# LM2596.net
KiCad netlist of a schematic drawn in Altium Designer
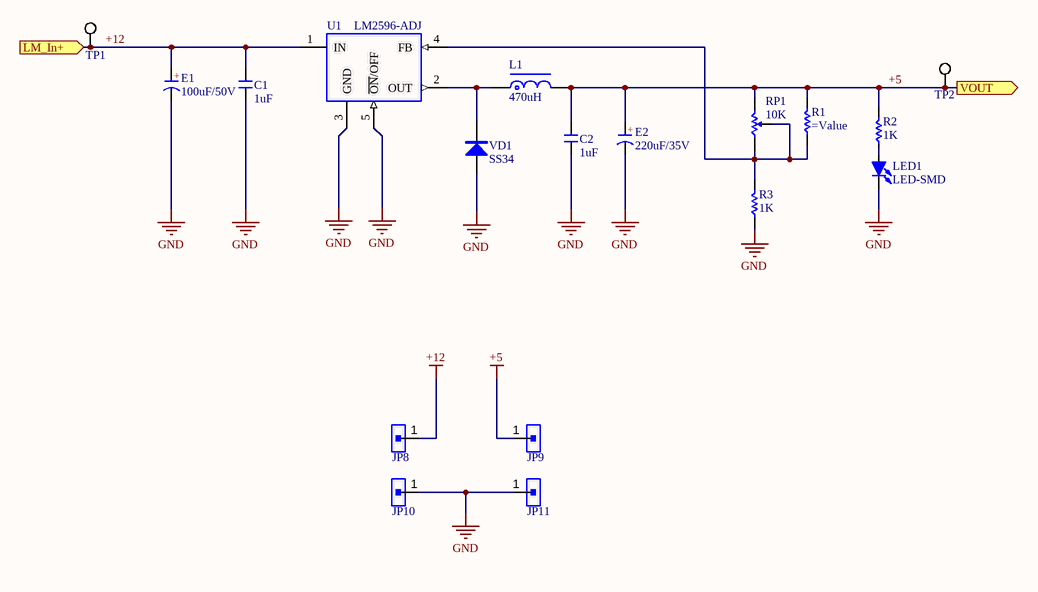
[diagram p0: LM2596.SchDoc]

(export (version "E")
  (design (tool "Eeschema 10.0.6"))
  (components
    (comp (ref "C1")
      (value "1uF")
      (footprint "C 0805")
      (description "Non-polar patch capacitor")
      (fields (field (name "版权归属") "源创客"))
      (libsource (lib "Passive (Resistor-Capacitor-Inductor-Veristor-Ferrite)") (part "C"))
    )
    (comp (ref "C2")
      (value "1uF")
      (footprint "C 0805")
      (description "Non-polar patch capacitor")
      (fields (field (name "版权归属") "源创客"))
      (libsource (lib "Passive (Resistor-Capacitor-Inductor-Veristor-Ferrite)") (part "C"))
    )
    (comp (ref "E1")
      (value "100uF/50V")
      (footprint "CM E(8*10.2)")
      (description "Chip electrolytic capacitor")
      (fields (field (name "版权归属") "源创客"))
      (libsource (lib "Passive (Resistor-Capacitor-Inductor-Veristor-Ferrite)") (part "C-CM"))
    )
    (comp (ref "E2")
      (value "220uF/35V")
      (footprint "CM E(8*10.2)")
      (description "Chip electrolytic capacitor")
      (fields (field (name "版权归属") "源创客"))
      (libsource (lib "Passive (Resistor-Capacitor-Inductor-Veristor-Ferrite)") (part "C-CM"))
    )
    (comp (ref "JP8")
      (value "HDR-1X1")
      (footprint "HDR-1X1")
      (description "1P Connector")
      (fields (field (name "版权归属") "源创客"))
      (libsource (lib "") (part "Header 1_1"))
    )
    (comp (ref "JP9")
      (value "HDR-1X1")
      (footprint "HDR-1X1")
      (description "1P Connector")
      (fields (field (name "版权归属") "源创客"))
      (libsource (lib "Connectors") (part "Header 1"))
    )
    (comp (ref "JP10")
      (value "HDR-1X1")
      (footprint "HDR-1X1")
      (description "1P Connector")
      (fields (field (name "版权归属") "源创客"))
      (libsource (lib "") (part "Header 1_1"))
    )
    (comp (ref "JP11")
      (value "HDR-1X1")
      (footprint "HDR-1X1")
      (description "1P Connector")
      (fields (field (name "版权归属") "源创客"))
      (libsource (lib "Connectors") (part "Header 1"))
    )
    (comp (ref "L1")
      (value "470uH")
      (footprint "CDRH127")
      (description "Power shielded inductor")
      (fields (field (name "版权归属") "源创客"))
      (libsource (lib "Passive (Resistor-Capacitor-Inductor-Veristor-Ferrite)") (part "L-CDRH"))
    )
    (comp (ref "LED1")
      (value "LED-SMD")
      (footprint "LED 0805R")
      (description "Patch LED")
      (fields (field (name "版权归属") "源创客"))
      (libsource (lib "LED") (part "LED-SMD"))
    )
    (comp (ref "R1")
      (value "~")
      (footprint "R 0805")
      (description "Chip resistor")
      (fields (field (name "版权归属") "源创客"))
      (libsource (lib "Passive (Resistor-Capacitor-Inductor-Veristor-Ferrite)") (part "R"))
    )
    (comp (ref "R2")
      (value "1K")
      (footprint "R 0805")
      (description "Chip resistor")
      (fields (field (name "版权归属") "源创客"))
      (libsource (lib "Passive (Resistor-Capacitor-Inductor-Veristor-Ferrite)") (part "R"))
    )
    (comp (ref "R3")
      (value "1K")
      (footprint "R 0805")
      (description "Chip resistor")
      (fields (field (name "版权归属") "源创客"))
      (libsource (lib "Passive (Resistor-Capacitor-Inductor-Veristor-Ferrite)") (part "R"))
    )
    (comp (ref "RP1")
      (value "10K")
      (footprint "3296W")
      (description "Plug-in potentiometer")
      (fields (field (name "版权归属") "源创客"))
      (libsource (lib "Passive (Resistor-Capacitor-Inductor-Veristor-Ferrite)") (part "RP-THD"))
    )
    (comp (ref "TP1")
      (value "Test Point Pad")
      (footprint "TP15")
      (fields (field (name "DESIGNER") "Eng. Saeid Jorablo"))
      (libsource (lib "Test Point") (part "Test Point Pad"))
    )
    (comp (ref "TP2")
      (value "Test Point Pad")
      (footprint "TP15")
      (fields (field (name "DESIGNER") "Eng. Saeid Jorablo"))
      (libsource (lib "Test Point") (part "Test Point Pad"))
    )
    (comp (ref "U1")
      (value "LM2596-ADJ")
      (footprint "TO263-5A")
      (description "DC step-down chip")
      (fields (field (name "版权归属") "源创客"))
      (libsource (lib "Integrated Circuit") (part "LM2596"))
    )
    (comp (ref "VD1")
      (value "SS34")
      (footprint "SMA")
      (description "Schottky diodes")
      (fields (field (name "版权归属") "源创客"))
      (libsource (lib "Diode-Zener-Rectifier Bridge") (part "SS34"))
    )
  )
  (nets
    (net (code "1") (name "+5") (class "Default")
      (node (ref "C2") (pin "2") (pinfunction "2_2") (pintype "passive"))
      (node (ref "E2") (pin "1") (pinfunction "A_1") (pintype "passive"))
      (node (ref "JP9") (pin "1") (pintype "passive"))
      (node (ref "L1") (pin "2") (pinfunction "2_2") (pintype "passive"))
      (node (ref "R1") (pin "2") (pinfunction "2_2") (pintype "passive"))
      (node (ref "R2") (pin "2") (pinfunction "2_2") (pintype "passive"))
      (node (ref "RP1") (pin "2") (pinfunction "2_2") (pintype "passive"))
      (node (ref "TP2") (pin "1") (pinfunction "1_1") (pintype "passive"))
    )
    (net (code "2") (name "+12") (class "Default")
      (node (ref "C1") (pin "2") (pinfunction "2_2") (pintype "passive"))
      (node (ref "E1") (pin "1") (pinfunction "A_1") (pintype "passive"))
      (node (ref "JP8") (pin "1") (pintype "passive"))
      (node (ref "TP1") (pin "1") (pinfunction "1_1") (pintype "passive"))
      (node (ref "U1") (pin "1") (pinfunction "IN_1") (pintype "power_in"))
    )
    (net (code "3") (name "GND") (class "Default")
      (node (ref "C1") (pin "1") (pinfunction "1_1") (pintype "passive"))
      (node (ref "C2") (pin "1") (pinfunction "1_1") (pintype "passive"))
      (node (ref "E1") (pin "2") (pinfunction "K_2") (pintype "passive"))
      (node (ref "E2") (pin "2") (pinfunction "K_2") (pintype "passive"))
      (node (ref "JP10") (pin "1") (pintype "passive"))
      (node (ref "JP11") (pin "1") (pintype "passive"))
      (node (ref "LED1") (pin "2") (pinfunction "K_2") (pintype "passive"))
      (node (ref "R3") (pin "1") (pinfunction "1_1") (pintype "passive"))
      (node (ref "U1") (pin "3") (pinfunction "GND_3") (pintype "power_in"))
      (node (ref "U1") (pin "5") (pinfunction "~{ON}/OFF_5") (pintype "input"))
      (node (ref "VD1") (pin "1") (pinfunction "A_1") (pintype "passive"))
    )
    (net (code "4") (name "Net-(LED1-A)") (class "Default")
      (node (ref "LED1") (pin "1") (pinfunction "A_1") (pintype "passive"))
      (node (ref "R2") (pin "1") (pinfunction "1_1") (pintype "passive"))
    )
    (net (code "5") (name "Net-(U1-FB)") (class "Default")
      (node (ref "R1") (pin "1") (pinfunction "1_1") (pintype "passive"))
      (node (ref "R3") (pin "2") (pinfunction "2_2") (pintype "passive"))
      (node (ref "RP1") (pin "1") (pinfunction "1_1") (pintype "passive"))
      (node (ref "RP1") (pin "ADJ") (pinfunction "ADJ_ADJ") (pintype "passive"))
      (node (ref "U1") (pin "4") (pinfunction "FB_4") (pintype "input"))
    )
    (net (code "6") (name "Net-(U1-OUT)") (class "Default")
      (node (ref "L1") (pin "1") (pinfunction "1_1") (pintype "passive"))
      (node (ref "U1") (pin "2") (pinfunction "OUT_2") (pintype "output"))
      (node (ref "VD1") (pin "2") (pinfunction "K_2") (pintype "passive"))
    )
  )
)
